# BMSMaster.net
KiCad netlist of a schematic drawn in EAGLE
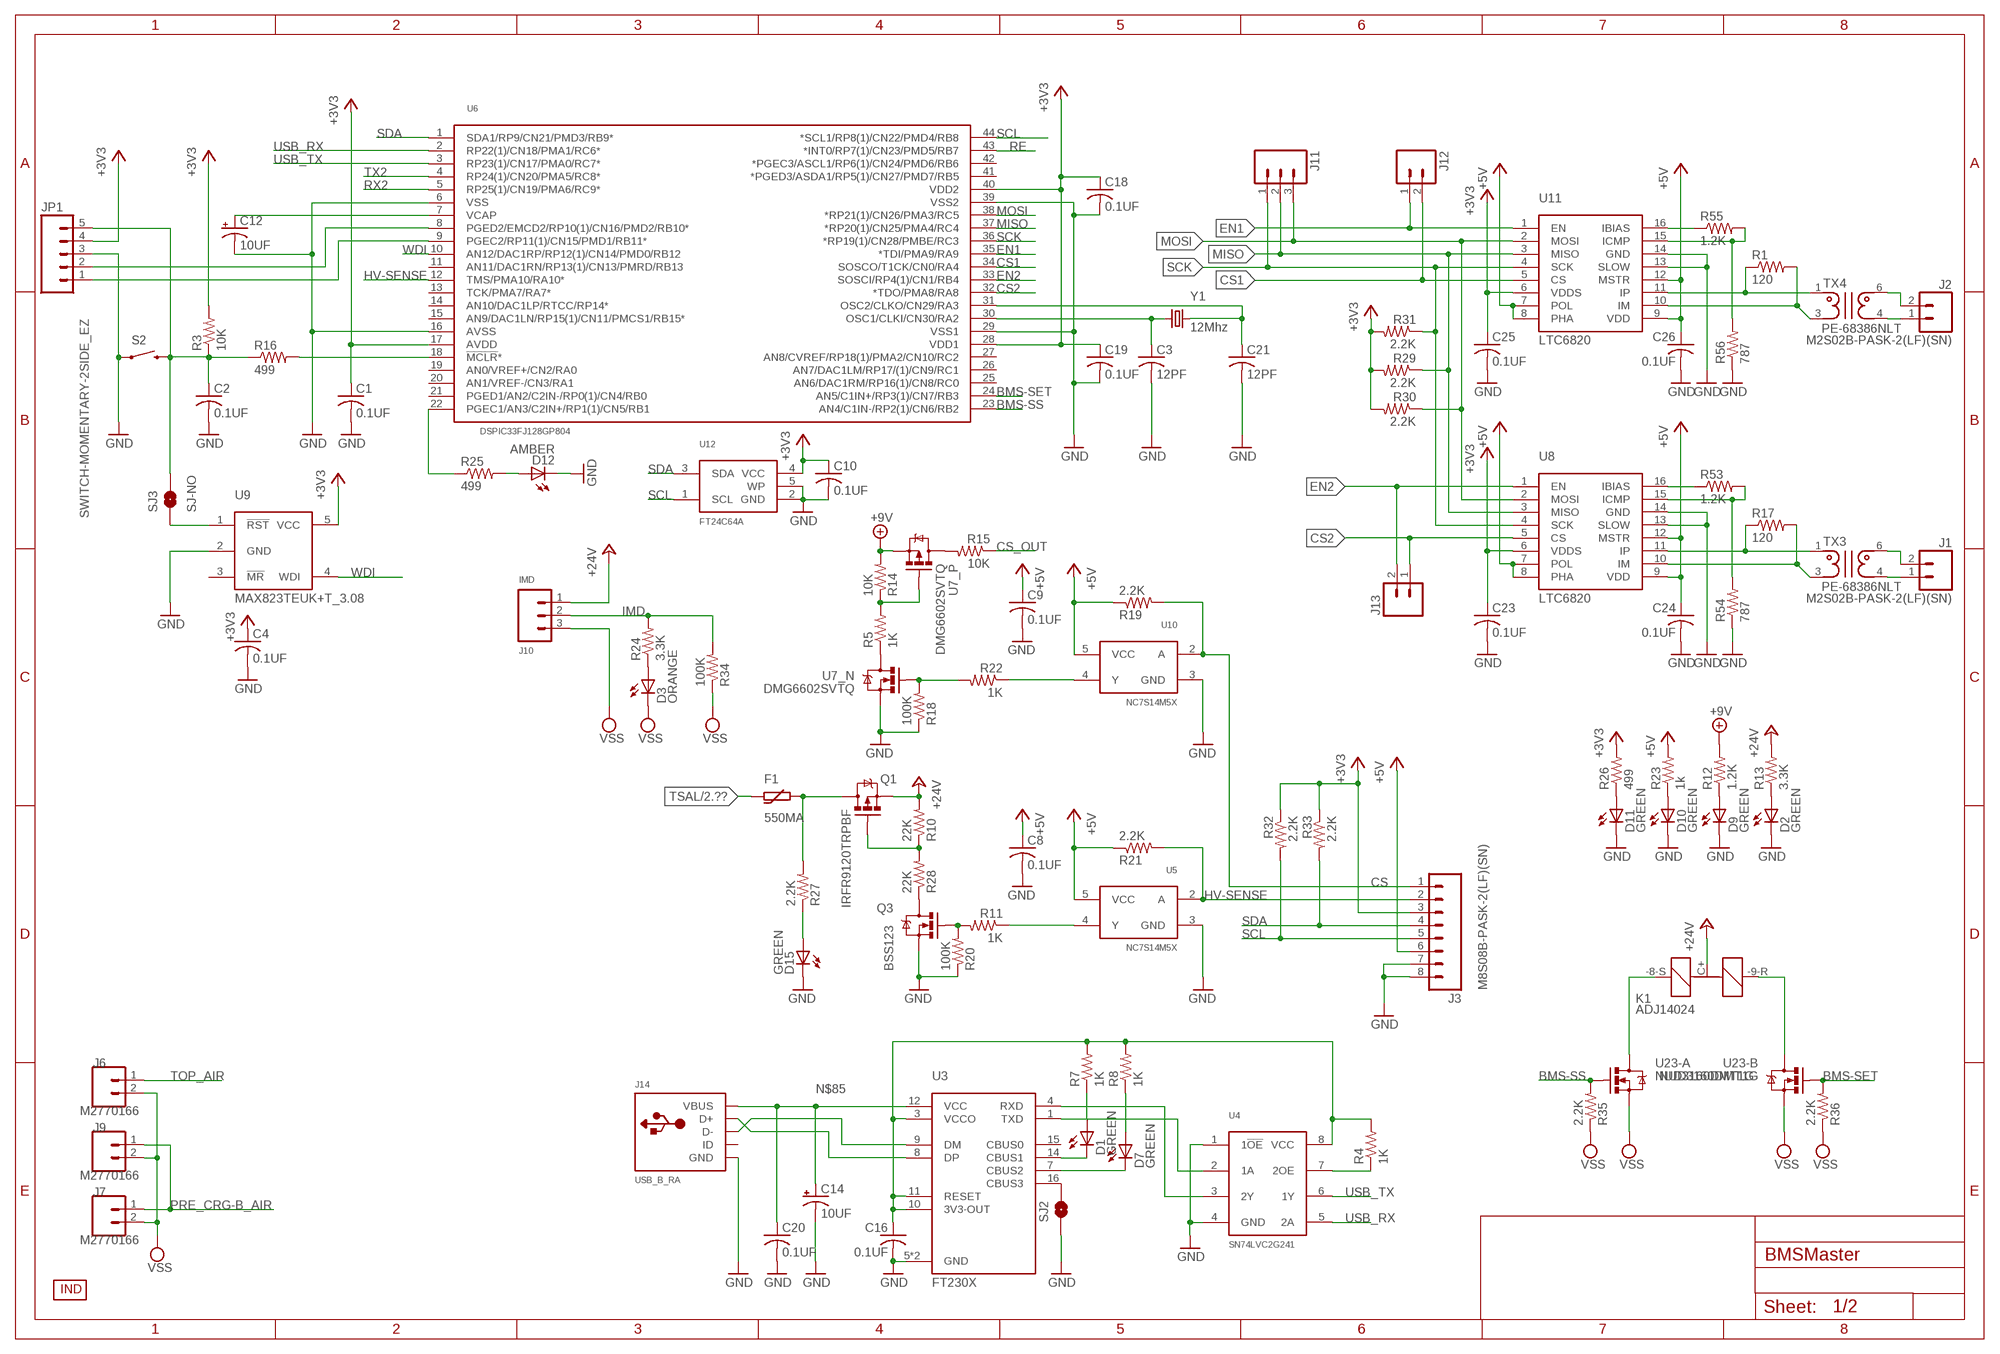
[diagram p0: schematic, sheet 1]
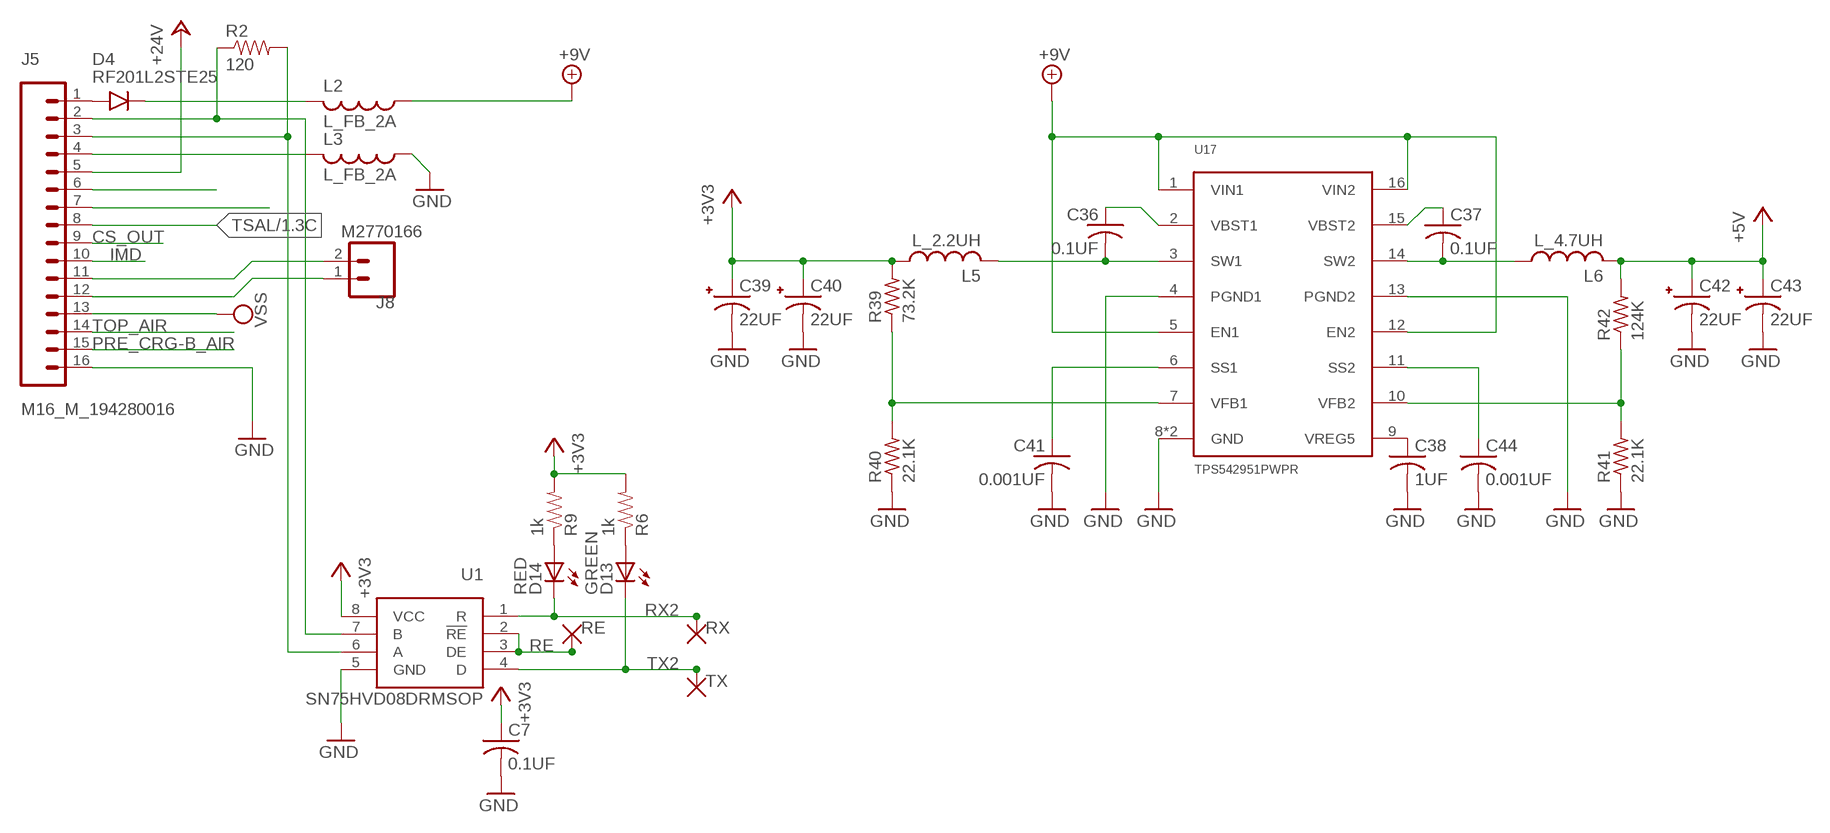
[diagram p1: schematic, sheet 2]

(export (version "E")
  (design (tool "Eeschema 10.0.6"))
  (components
    (comp (ref "C7")
      (value "0.1UF")
      (footprint "eagle-import:0805")
      (fields (field (name "PARTNO") "CC0805ZRY5V9BB104"))
      (libsource (lib "eagle-import") (part "CAP_0.1UF_50V_0805"))
    )
    (comp (ref "C36")
      (value "0.1UF")
      (footprint "eagle-import:R0603")
      (fields (field (name "PARTNO") "CC0603ZRY5V9BB104"))
      (libsource (lib "eagle-import") (part "C_0.1UF_50V"))
    )
    (comp (ref "C37")
      (value "0.1UF")
      (footprint "eagle-import:R0603")
      (fields (field (name "PARTNO") "CC0603ZRY5V9BB104"))
      (libsource (lib "eagle-import") (part "C_0.1UF_50V"))
    )
    (comp (ref "C38")
      (value "1UF")
      (footprint "eagle-import:R0603")
      (fields (field (name "PARTNO") "CL10B105MO8NNWC"))
      (libsource (lib "eagle-import") (part "C_1UF_16V"))
    )
    (comp (ref "C39")
      (value "22UF")
      (footprint "eagle-import:EIA7343")
      (fields (field (name "PARTNO") "T495D226K035ATE300"))
      (libsource (lib "eagle-import") (part "C-POL_22UF_35V"))
    )
    (comp (ref "C40")
      (value "22UF")
      (footprint "eagle-import:EIA7343")
      (fields (field (name "PARTNO") "T495D226K035ATE300"))
      (libsource (lib "eagle-import") (part "C-POL_22UF_35V"))
    )
    (comp (ref "C41")
      (value "0.001UF")
      (footprint "eagle-import:R0603")
      (fields (field (name "PARTNO") "GRM188R71H103KA01D"))
      (libsource (lib "eagle-import") (part "C_0.001UF_50V"))
    )
    (comp (ref "C42")
      (value "22UF")
      (footprint "eagle-import:EIA7343")
      (fields (field (name "PARTNO") "T495D226K035ATE300"))
      (libsource (lib "eagle-import") (part "C-POL_22UF_35V"))
    )
    (comp (ref "C43")
      (value "22UF")
      (footprint "eagle-import:EIA7343")
      (fields (field (name "PARTNO") "T495D226K035ATE300"))
      (libsource (lib "eagle-import") (part "C-POL_22UF_35V"))
    )
    (comp (ref "C44")
      (value "0.001UF")
      (footprint "eagle-import:R0603")
      (fields (field (name "PARTNO") "GRM188R71H103KA01D"))
      (libsource (lib "eagle-import") (part "C_0.001UF_50V"))
    )
    (comp (ref "D4")
      (value "RF201L2STE25")
      (footprint "eagle-import:SMA")
      (libsource (lib "eagle-import") (part "DIODE_RF201L2STE25"))
    )
    (comp (ref "D13")
      (value "GREEN")
      (footprint "eagle-import:CHIP_LED0805")
      (fields (field (name "PARTNO") "LTST-S220GKT"))
      (libsource (lib "eagle-import") (part "LED_GREEN"))
    )
    (comp (ref "D14")
      (value "RED")
      (footprint "eagle-import:CHIP_LED0805")
      (fields (field (name "PARTNO") "LH R974-LP-1"))
      (libsource (lib "eagle-import") (part "LED_RED"))
    )
    (comp (ref "J5")
      (value "M16_M_194280016")
      (footprint "eagle-import:19428-0016")
      (fields (field (name "PARTNO") "0194280016"))
      (libsource (lib "eagle-import") (part "M16_M_194280016"))
    )
    (comp (ref "J8")
      (value "M2770166")
      (footprint "eagle-import:1-770166-0")
      (fields (field (name "PARTNO") "1-770166-0"))
      (libsource (lib "eagle-import") (part "M2770166"))
    )
    (comp (ref "L2")
      (value "L_FB_2A")
      (footprint "eagle-import:0805")
      (fields (field (name "PARTNO") "FBMH2012HM121-T"))
      (libsource (lib "eagle-import") (part "L_FB_2A"))
    )
    (comp (ref "L3")
      (value "L_FB_2A")
      (footprint "eagle-import:0805")
      (fields (field (name "PARTNO") "FBMH2012HM121-T"))
      (libsource (lib "eagle-import") (part "L_FB_2A"))
    )
    (comp (ref "L5")
      (value "L_2.2UH")
      (footprint "eagle-import:LQH43")
      (fields (field (name "PARTNO") "LQH43PN2R2M26L"))
      (libsource (lib "eagle-import") (part "L_2.2UH"))
    )
    (comp (ref "L6")
      (value "L_4.7UH")
      (footprint "eagle-import:LQH43")
      (fields (field (name "PARTNO") " LQH43PN4R7M26L"))
      (libsource (lib "eagle-import") (part "L_4.7UH"))
    )
    (comp (ref "R2")
      (value "120")
      (footprint "eagle-import:0805")
      (fields (field (name "PARTNO") "RC0805FR-07120RL"))
      (libsource (lib "eagle-import") (part "RES_120_1%_0805"))
    )
    (comp (ref "R6")
      (value "1k")
      (footprint "eagle-import:0805")
      (fields (field (name "PARTNO") "RC0805FR-071KL"))
      (libsource (lib "eagle-import") (part "RES_1K_1%_0805"))
    )
    (comp (ref "R9")
      (value "1k")
      (footprint "eagle-import:0805")
      (fields (field (name "PARTNO") "RC0805FR-071KL"))
      (libsource (lib "eagle-import") (part "RES_1K_1%_0805"))
    )
    (comp (ref "R39")
      (value "73.2K")
      (footprint "eagle-import:R0805")
      (fields (field (name "PARTNO") " RC0805FR-0773K2L"))
      (libsource (lib "eagle-import") (part "R_73.2K_1%"))
    )
    (comp (ref "R40")
      (value "22.1K")
      (footprint "eagle-import:R0805")
      (fields (field (name "PARTNO") "RC0805FR-0722K1L"))
      (libsource (lib "eagle-import") (part "R_22.1K_1%"))
    )
    (comp (ref "R41")
      (value "22.1K")
      (footprint "eagle-import:R0805")
      (fields (field (name "PARTNO") "RC0805FR-0722K1L"))
      (libsource (lib "eagle-import") (part "R_22.1K_1%"))
    )
    (comp (ref "R42")
      (value "124K")
      (footprint "eagle-import:R0805")
      (fields (field (name "PARTNO") "RC0805FR-07124KL"))
      (libsource (lib "eagle-import") (part "R_124K_1%"))
    )
    (comp (ref "RE")
      (value "TP")
      (footprint "eagle-import:0603")
      (fields (field (name "PARTNO") "1625854-3"))
      (libsource (lib "eagle-import") (part "TP"))
    )
    (comp (ref "RX")
      (value "TP")
      (footprint "eagle-import:0603")
      (fields (field (name "PARTNO") "1625854-3"))
      (libsource (lib "eagle-import") (part "TP"))
    )
    (comp (ref "TX")
      (value "TP")
      (footprint "eagle-import:0603")
      (fields (field (name "PARTNO") "1625854-3"))
      (libsource (lib "eagle-import") (part "TP"))
    )
    (comp (ref "U1")
      (value "SN75HVD08DRMSOP")
      (footprint "eagle-import:MSOP-8")
      (fields (field (name "PARTNO") "ISL83072EIUZA-T"))
      (libsource (lib "eagle-import") (part "SN75HVD08DRMSOP"))
    )
    (comp (ref "U17")
      (value "TPS542951PWPR")
      (footprint "eagle-import:TSSOP-16")
      (libsource (lib "eagle-import") (part "TPS542951PWPR"))
    )
    (comp (ref "C1")
      (value "0.1UF")
      (footprint "eagle-import:0805")
      (fields (field (name "PARTNO") "CC0805ZRY5V9BB104"))
      (libsource (lib "eagle-import") (part "CAP_0.1UF_50V_0805"))
    )
    (comp (ref "C2")
      (value "0.1UF")
      (footprint "eagle-import:0805")
      (fields (field (name "PARTNO") "CC0805ZRY5V9BB104"))
      (libsource (lib "eagle-import") (part "CAP_0.1UF_50V_0805"))
    )
    (comp (ref "C3")
      (value "12PF")
      (footprint "eagle-import:0805")
      (fields (field (name "PARTNO") "CL21C120JBANNNC"))
      (libsource (lib "eagle-import") (part "CAP_12PF_50V_0805"))
    )
    (comp (ref "C4")
      (value "0.1UF")
      (footprint "eagle-import:0805")
      (fields (field (name "PARTNO") "CC0805ZRY5V9BB104"))
      (libsource (lib "eagle-import") (part "CAP_0.1UF_50V_0805"))
    )
    (comp (ref "C8")
      (value "0.1UF")
      (footprint "eagle-import:0805")
      (fields (field (name "PARTNO") "CC0805ZRY5V9BB104"))
      (libsource (lib "eagle-import") (part "CAP_0.1UF_50V_0805"))
    )
    (comp (ref "C9")
      (value "0.1UF")
      (footprint "eagle-import:0805")
      (fields (field (name "PARTNO") "CC0805ZRY5V9BB104"))
      (libsource (lib "eagle-import") (part "CAP_0.1UF_50V_0805"))
    )
    (comp (ref "C10")
      (value "0.1UF")
      (footprint "eagle-import:0805")
      (fields (field (name "PARTNO") "CC0805ZRY5V9BB104"))
      (libsource (lib "eagle-import") (part "CAP_0.1UF_50V_0805"))
    )
    (comp (ref "C12")
      (value "10UF")
      (footprint "eagle-import:EIA3216-16V")
      (fields (field (name "PARTNO") "T491A106M016AT"))
      (libsource (lib "eagle-import") (part "CAP-POL_10UF_16V"))
    )
    (comp (ref "C14")
      (value "10UF")
      (footprint "eagle-import:EIA3216-16V")
      (fields (field (name "PARTNO") "T491A106M016AT"))
      (libsource (lib "eagle-import") (part "CAP-POL_10UF_16V"))
    )
    (comp (ref "C16")
      (value "0.1UF")
      (footprint "eagle-import:0805")
      (fields (field (name "PARTNO") "CC0805ZRY5V9BB104"))
      (libsource (lib "eagle-import") (part "CAP_0.1UF_50V_0805"))
    )
    (comp (ref "C18")
      (value "0.1UF")
      (footprint "eagle-import:0805")
      (fields (field (name "PARTNO") "CC0805ZRY5V9BB104"))
      (libsource (lib "eagle-import") (part "CAP_0.1UF_50V_0805"))
    )
    (comp (ref "C19")
      (value "0.1UF")
      (footprint "eagle-import:0805")
      (fields (field (name "PARTNO") "CC0805ZRY5V9BB104"))
      (libsource (lib "eagle-import") (part "CAP_0.1UF_50V_0805"))
    )
    (comp (ref "C20")
      (value "0.1UF")
      (footprint "eagle-import:0805")
      (fields (field (name "PARTNO") "CC0805ZRY5V9BB104"))
      (libsource (lib "eagle-import") (part "CAP_0.1UF_50V_0805"))
    )
    (comp (ref "C21")
      (value "12PF")
      (footprint "eagle-import:0805")
      (fields (field (name "PARTNO") "CL21C120JBANNNC"))
      (libsource (lib "eagle-import") (part "CAP_12PF_50V_0805"))
    )
    (comp (ref "C23")
      (value "0.1UF")
      (footprint "eagle-import:0805")
      (fields (field (name "PARTNO") "CC0805ZRY5V9BB104"))
      (libsource (lib "eagle-import") (part "CAP_0.1UF_50V_0805"))
    )
    (comp (ref "C24")
      (value "0.1UF")
      (footprint "eagle-import:0805")
      (fields (field (name "PARTNO") "CC0805ZRY5V9BB104"))
      (libsource (lib "eagle-import") (part "CAP_0.1UF_50V_0805"))
    )
    (comp (ref "C25")
      (value "0.1UF")
      (footprint "eagle-import:0805")
      (fields (field (name "PARTNO") "CC0805ZRY5V9BB104"))
      (libsource (lib "eagle-import") (part "CAP_0.1UF_50V_0805"))
    )
    (comp (ref "C26")
      (value "0.1UF")
      (footprint "eagle-import:0805")
      (fields (field (name "PARTNO") "CC0805ZRY5V9BB104"))
      (libsource (lib "eagle-import") (part "CAP_0.1UF_50V_0805"))
    )
    (comp (ref "D1")
      (value "GREEN")
      (footprint "eagle-import:CHIP_LED0805")
      (fields (field (name "PARTNO") "LTST-S220GKT"))
      (libsource (lib "eagle-import") (part "LED_GREEN"))
    )
    (comp (ref "D2")
      (value "GREEN")
      (footprint "eagle-import:CHIP_LED0805")
      (fields (field (name "PARTNO") "LTST-S220GKT"))
      (libsource (lib "eagle-import") (part "LED_GREEN"))
    )
    (comp (ref "D3")
      (value "ORANGE")
      (footprint "eagle-import:CHIP_LED0805")
      (fields (field (name "PARTNO") "LTST-C170KFKT"))
      (libsource (lib "eagle-import") (part "LED_ORANGE"))
    )
    (comp (ref "D7")
      (value "GREEN")
      (footprint "eagle-import:CHIP_LED0805")
      (fields (field (name "PARTNO") "LTST-S220GKT"))
      (libsource (lib "eagle-import") (part "LED_GREEN"))
    )
    (comp (ref "D9")
      (value "GREEN")
      (footprint "eagle-import:CHIP_LED0805")
      (fields (field (name "PARTNO") "LTST-S220GKT"))
      (libsource (lib "eagle-import") (part "LED_GREEN"))
    )
    (comp (ref "D10")
      (value "GREEN")
      (footprint "eagle-import:CHIP_LED0805")
      (fields (field (name "PARTNO") "LTST-S220GKT"))
      (libsource (lib "eagle-import") (part "LED_GREEN"))
    )
    (comp (ref "D11")
      (value "GREEN")
      (footprint "eagle-import:CHIP_LED0805")
      (fields (field (name "PARTNO") "LTST-S220GKT"))
      (libsource (lib "eagle-import") (part "LED_GREEN"))
    )
    (comp (ref "D12")
      (value "AMBER")
      (footprint "eagle-import:CHIP_LED0805")
      (fields (field (name "PARTNO") "HSMA-C170"))
      (libsource (lib "eagle-import") (part "LED_AMBER"))
    )
    (comp (ref "D15")
      (value "GREEN")
      (footprint "eagle-import:CHIP_LED0805")
      (fields (field (name "PARTNO") "LTST-S220GKT"))
      (libsource (lib "eagle-import") (part "LED_GREEN"))
    )
    (comp (ref "F1")
      (value "550MA")
      (footprint "eagle-import:2018")
      (fields (field (name "PARTNO") "MF-SMDF050-2"))
      (libsource (lib "eagle-import") (part "PTC_550MA_60V"))
    )
    (comp (ref "J1")
      (value "M2S02B-PASK-2(LF)(SN)")
      (footprint "eagle-import:S02B-PASK-2(LF)(SN)")
      (fields (field (name "PARTNO") "S02B-PASK-2(LF)(SN)"))
      (libsource (lib "eagle-import") (part "M2S02B-PASK-2(LF)(SN)"))
    )
    (comp (ref "J2")
      (value "M2S02B-PASK-2(LF)(SN)")
      (footprint "eagle-import:S02B-PASK-2(LF)(SN)")
      (fields (field (name "PARTNO") "S02B-PASK-2(LF)(SN)"))
      (libsource (lib "eagle-import") (part "M2S02B-PASK-2(LF)(SN)"))
    )
    (comp (ref "J3")
      (value "M8S08B-PASK-2(LF)(SN)")
      (footprint "eagle-import:S08B-PASK-2(LF)(SN)")
      (fields (field (name "PARTNO") "S08B-PASK-2(LF)(SN)"))
      (libsource (lib "eagle-import") (part "M8S08B-PASK-2(LF)(SN)"))
    )
    (comp (ref "J6")
      (value "M2770166")
      (footprint "eagle-import:1-770166-0")
      (fields (field (name "PARTNO") "1-770166-0"))
      (libsource (lib "eagle-import") (part "M2770166"))
    )
    (comp (ref "J7")
      (value "M2770166")
      (footprint "eagle-import:1-770166-0")
      (fields (field (name "PARTNO") "1-770166-0"))
      (libsource (lib "eagle-import") (part "M2770166"))
    )
    (comp (ref "J9")
      (value "M2770166")
      (footprint "eagle-import:1-770166-0")
      (fields (field (name "PARTNO") "1-770166-0"))
      (libsource (lib "eagle-import") (part "M2770166"))
    )
    (comp (ref "J10")
      (value "IMD")
      (footprint "eagle-import:MOLEX-1X3")
      (fields (field (name "PARTNO") "0022232031"))
      (libsource (lib "eagle-import") (part "M3M1X3"))
    )
    (comp (ref "J11")
      (value "M03LOCK_LONGPADS")
      (footprint "eagle-import:1X03_LOCK_LONGPADS")
      (libsource (lib "eagle-import") (part "M03LOCK_LONGPADS"))
    )
    (comp (ref "J12")
      (value "M02LOCK_LONGPADS")
      (footprint "eagle-import:1X02_LOCK_LONGPADS")
      (libsource (lib "eagle-import") (part "M02LOCK_LONGPADS"))
    )
    (comp (ref "J13")
      (value "M02LOCK_LONGPADS")
      (footprint "eagle-import:1X02_LOCK_LONGPADS")
      (libsource (lib "eagle-import") (part "M02LOCK_LONGPADS"))
    )
    (comp (ref "J14")
      (value "USB_B_RA")
      (footprint "eagle-import:USB-B1HSW6")
      (fields (field (name "PARTNO") "USB-B1HSW6"))
      (libsource (lib "eagle-import") (part "USB_B_RA"))
    )
    (comp (ref "JP1")
      (value "M05LOCK_LONGPADS")
      (footprint "eagle-import:1X05_LOCK_LONGPADS")
      (libsource (lib "eagle-import") (part "M05LOCK_LONGPADS"))
    )
    (comp (ref "K1")
      (value "ADJ14024")
      (footprint "eagle-import:ADJ14024")
      (libsource (lib "eagle-import") (part "ADJ14024"))
    )
    (comp (ref "Q1")
      (value "IRFR9120TRPBF")
      (footprint "eagle-import:DPAK")
      (libsource (lib "eagle-import") (part "MOS-P_IRFR9120TRPBF"))
    )
    (comp (ref "Q3")
      (value "BSS123")
      (footprint "eagle-import:SOT23")
      (fields (field (name "PARTNO") "BSS123,215"))
      (libsource (lib "eagle-import") (part "MOS-N_BSS123"))
    )
    (comp (ref "R1")
      (value "120")
      (footprint "eagle-import:0805")
      (fields (field (name "PARTNO") "RC0805FR-07120RL"))
      (libsource (lib "eagle-import") (part "RES_120_1%_0805"))
    )
    (comp (ref "R3")
      (value "10K")
      (footprint "eagle-import:0805")
      (fields (field (name "PARTNO") "RC0805FR-0710KL"))
      (libsource (lib "eagle-import") (part "RES_10K_1%_0805"))
    )
    (comp (ref "R4")
      (value "1K")
      (footprint "eagle-import:0805")
      (fields (field (name "PARTNO") "RC0805FR-071KL"))
      (libsource (lib "eagle-import") (part "RES_1K_1%_0805"))
    )
    (comp (ref "R5")
      (value "1K")
      (footprint "eagle-import:0805")
      (fields (field (name "PARTNO") "RC0805FR-071KL"))
      (libsource (lib "eagle-import") (part "RES_1K_1%_0805"))
    )
    (comp (ref "R7")
      (value "1K")
      (footprint "eagle-import:0805")
      (fields (field (name "PARTNO") "RC0805FR-071KL"))
      (libsource (lib "eagle-import") (part "RES_1K_1%_0805"))
    )
    (comp (ref "R8")
      (value "1K")
      (footprint "eagle-import:0805")
      (fields (field (name "PARTNO") "RC0805FR-071KL"))
      (libsource (lib "eagle-import") (part "RES_1K_1%_0805"))
    )
    (comp (ref "R10")
      (value "22K")
      (footprint "eagle-import:0805")
      (fields (field (name "PARTNO") "RC0805FR-0722KL"))
      (libsource (lib "eagle-import") (part "RES_22K_1%_0805"))
    )
    (comp (ref "R11")
      (value "1K")
      (footprint "eagle-import:0805")
      (fields (field (name "PARTNO") "RC0805FR-071KL"))
      (libsource (lib "eagle-import") (part "RES_1K_1%_0805"))
    )
    (comp (ref "R12")
      (value "1.2K")
      (footprint "eagle-import:0805")
      (fields (field (name "PARTNO") "RC0805FR-071K2L"))
      (libsource (lib "eagle-import") (part "RES_1.2K_1%_0805"))
    )
    (comp (ref "R13")
      (value "3.3K")
      (footprint "eagle-import:0805")
      (fields (field (name "PARTNO") "RC0805FR-073K3L"))
      (libsource (lib "eagle-import") (part "RES_3.3K_1%_0805"))
    )
    (comp (ref "R14")
      (value "10K")
      (footprint "eagle-import:0805")
      (fields (field (name "PARTNO") "RC0805FR-0710KL"))
      (libsource (lib "eagle-import") (part "RES_10K_1%_0805"))
    )
    (comp (ref "R15")
      (value "10K")
      (footprint "eagle-import:0805")
      (fields (field (name "PARTNO") "RC0805FR-0710KL"))
      (libsource (lib "eagle-import") (part "RES_10K_1%_0805"))
    )
    (comp (ref "R16")
      (value "499")
      (footprint "eagle-import:0805")
      (fields (field (name "PARTNO") "RC0805FR-07499RL"))
      (libsource (lib "eagle-import") (part "RES_499_1%_0805"))
    )
    (comp (ref "R17")
      (value "120")
      (footprint "eagle-import:0805")
      (fields (field (name "PARTNO") "RC0805FR-07120RL"))
      (libsource (lib "eagle-import") (part "RES_120_1%_0805"))
    )
    (comp (ref "R18")
      (value "100K")
      (footprint "eagle-import:0805")
      (fields (field (name "PARTNO") "RC0805FR-07100KL"))
      (libsource (lib "eagle-import") (part "RES_100K_1%_0805"))
    )
    (comp (ref "R19")
      (value "2.2K")
      (footprint "eagle-import:0805")
      (fields (field (name "PARTNO") "RC0805FR-072K2L"))
      (libsource (lib "eagle-import") (part "RES_2.2K_1%_0805"))
    )
    (comp (ref "R20")
      (value "100K")
      (footprint "eagle-import:0805")
      (fields (field (name "PARTNO") "RC0805FR-07100KL"))
      (libsource (lib "eagle-import") (part "RES_100K_1%_0805"))
    )
    (comp (ref "R21")
      (value "2.2K")
      (footprint "eagle-import:0805")
      (fields (field (name "PARTNO") "RC0805FR-072K2L"))
      (libsource (lib "eagle-import") (part "RES_2.2K_1%_0805"))
    )
    (comp (ref "R22")
      (value "1K")
      (footprint "eagle-import:0805")
      (fields (field (name "PARTNO") "RC0805FR-071KL"))
      (libsource (lib "eagle-import") (part "RES_1K_1%_0805"))
    )
    (comp (ref "R23")
      (value "1k")
      (footprint "eagle-import:0805")
      (fields (field (name "PARTNO") "RC0805FR-071KL"))
      (libsource (lib "eagle-import") (part "RES_1K_1%_0805"))
    )
    (comp (ref "R24")
      (value "3.3K")
      (footprint "eagle-import:0805")
      (fields (field (name "PARTNO") "RC0805FR-073K3L"))
      (libsource (lib "eagle-import") (part "RES_3.3K_1%_0805"))
    )
    (comp (ref "R25")
      (value "499")
      (footprint "eagle-import:0805")
      (fields (field (name "PARTNO") "RC0805FR-07499RL"))
      (libsource (lib "eagle-import") (part "RES_499_1%_0805"))
    )
    (comp (ref "R26")
      (value "499")
      (footprint "eagle-import:0805")
      (fields (field (name "PARTNO") "RC0805FR-07499RL"))
      (libsource (lib "eagle-import") (part "RES_499_1%_0805"))
    )
    (comp (ref "R27")
      (value "2.2K")
      (footprint "eagle-import:0805")
      (fields (field (name "PARTNO") "RC0805FR-072K2L"))
      (libsource (lib "eagle-import") (part "RES_2.2K_1%_0805"))
    )
    (comp (ref "R28")
      (value "22K")
      (footprint "eagle-import:0805")
      (fields (field (name "PARTNO") "RC0805FR-0722KL"))
      (libsource (lib "eagle-import") (part "RES_22K_1%_0805"))
    )
    (comp (ref "R29")
      (value "2.2K")
      (footprint "eagle-import:0805")
      (fields (field (name "PARTNO") "RC0805FR-072K2L"))
      (libsource (lib "eagle-import") (part "RES_2.2K_1%_0805"))
    )
    (comp (ref "R30")
      (value "2.2K")
      (footprint "eagle-import:0805")
      (fields (field (name "PARTNO") "RC0805FR-072K2L"))
      (libsource (lib "eagle-import") (part "RES_2.2K_1%_0805"))
    )
    (comp (ref "R31")
      (value "2.2K")
      (footprint "eagle-import:0805")
      (fields (field (name "PARTNO") "RC0805FR-072K2L"))
      (libsource (lib "eagle-import") (part "RES_2.2K_1%_0805"))
    )
    (comp (ref "R32")
      (value "2.2K")
      (footprint "eagle-import:0805")
      (fields (field (name "PARTNO") "RC0805FR-072K2L"))
      (libsource (lib "eagle-import") (part "RES_2.2K_1%_0805"))
    )
    (comp (ref "R33")
      (value "2.2K")
      (footprint "eagle-import:0805")
      (fields (field (name "PARTNO") "RC0805FR-072K2L"))
      (libsource (lib "eagle-import") (part "RES_2.2K_1%_0805"))
    )
    (comp (ref "R34")
      (value "100K")
      (footprint "eagle-import:0805")
      (fields (field (name "PARTNO") "RC0805FR-07100KL"))
      (libsource (lib "eagle-import") (part "RES_100K_1%_0805"))
    )
    (comp (ref "R35")
      (value "2.2K")
      (footprint "eagle-import:0805")
      (fields (field (name "PARTNO") "RC0805FR-072K2L"))
      (libsource (lib "eagle-import") (part "RES_2.2K_1%_0805"))
    )
    (comp (ref "R36")
      (value "2.2K")
      (footprint "eagle-import:0805")
      (fields (field (name "PARTNO") "RC0805FR-072K2L"))
      (libsource (lib "eagle-import") (part "RES_2.2K_1%_0805"))
    )
    (comp (ref "R53")
      (value "1.2K")
      (footprint "eagle-import:0805")
      (fields (field (name "PARTNO") "RC0805FR-071K2L"))
      (libsource (lib "eagle-import") (part "RES_1.2K_1%_0805"))
    )
    (comp (ref "R54")
      (value "787")
      (footprint "eagle-import:0805")
      (fields (field (name "PARTNO") "RC0805FR-07787RL"))
      (libsource (lib "eagle-import") (part "RES_787_1%"))
    )
    (comp (ref "R55")
      (value "1.2K")
      (footprint "eagle-import:0805")
      (fields (field (name "PARTNO") "RC0805FR-071K2L"))
      (libsource (lib "eagle-import") (part "RES_1.2K_1%_0805"))
    )
    (comp (ref "R56")
      (value "787")
      (footprint "eagle-import:0805")
      (fields (field (name "PARTNO") "RC0805FR-07787RL"))
      (libsource (lib "eagle-import") (part "RES_787_1%"))
    )
    (comp (ref "S2")
      (value "SWITCH-MOMENTARY-2SIDE_EZ")
      (footprint "eagle-import:TACTILE-PTH-SIDEEZ")
      (fields (field (name "PARTNO") "3-1825910-5"))
      (libsource (lib "eagle-import") (part "SWITCH-MOMENTARY-2SIDE_EZ"))
    )
    (comp (ref "SJ2")
      (value "JUMPER-PAD-2-NOYES_SILK")
      (footprint "eagle-import:PAD-JUMPER-2-NO_YES_SILK")
      (libsource (lib "eagle-import") (part "JUMPER-PAD-2-NOYES_SILK"))
    )
    (comp (ref "SJ3")
      (value "SJ-NO")
      (footprint "eagle-import:SJ_2S-NO")
      (libsource (lib "eagle-import") (part "SOLDERJUMPERNO"))
    )
    (comp (ref "TX3")
      (value "PE-68386NLT")
      (footprint "eagle-import:PE-68386NLT")
      (libsource (lib "eagle-import") (part "PE-68386NLT"))
    )
    (comp (ref "TX4")
      (value "PE-68386NLT")
      (footprint "eagle-import:PE-68386NLT")
      (libsource (lib "eagle-import") (part "PE-68386NLT"))
    )
    (comp (ref "U$1")
      (value "INDPK1")
      (footprint "eagle-import:PICKIT-PIN-1")
      (libsource (lib "eagle-import") (part "INDPK1"))
    )
    (comp (ref "U3")
      (value "FT230X")
      (footprint "eagle-import:SSOP-16")
      (fields (field (name "PARTNO") "FT230XS-R"))
      (libsource (lib "eagle-import") (part "FT230X"))
    )
    (comp (ref "U4")
      (value "SN74LVC2G241")
      (footprint "eagle-import:VFSOP-8")
      (fields (field (name "PARTNO") "SN74LVC2G241DCUR"))
      (libsource (lib "eagle-import") (part "SN74LVC2G241"))
    )
    (comp (ref "U5")
      (value "NC7S14M5X")
      (footprint "eagle-import:SOT23-5")
      (libsource (lib "eagle-import") (part "NC7S14M5X"))
    )
    (comp (ref "U6")
      (value "DSPIC33FJ128GP804")
      (footprint "eagle-import:TQFP-44")
      (fields (field (name "PARTNO") "DSPIC33FJ128GP804-I/PT"))
      (libsource (lib "eagle-import") (part "DSPIC33FJ128GP804"))
    )
    (comp (ref "U7")
      (value "DMG6602SVTQ")
      (footprint "eagle-import:SOT23-6")
      (fields (field (name "PARTNO") "DMG6602SVTQ-7"))
      (libsource (lib "eagle-import") (part "DMG6602SVTQ"))
    )
    (comp (ref "U8")
      (value "LTC6820")
      (footprint "eagle-import:MSOP-16")
      (fields (field (name "PARTNO") "LTC6820IMS#PBF"))
      (libsource (lib "eagle-import") (part "LTC6820"))
    )
    (comp (ref "U9")
      (value "MAX823TEUK+T_3.08")
      (footprint "eagle-import:SOT23-5")
      (fields (field (name "PARTNO") "MAX823TEUK+T"))
      (libsource (lib "eagle-import") (part "MAX823TEUK+T_3.08"))
    )
    (comp (ref "U10")
      (value "NC7S14M5X")
      (footprint "eagle-import:SOT23-5")
      (libsource (lib "eagle-import") (part "NC7S14M5X"))
    )
    (comp (ref "U11")
      (value "LTC6820")
      (footprint "eagle-import:MSOP-16")
      (fields (field (name "PARTNO") "LTC6820IMS#PBF"))
      (libsource (lib "eagle-import") (part "LTC6820"))
    )
    (comp (ref "U12")
      (value "FT24C64A")
      (footprint "eagle-import:SOT23-5")
      (fields (field (name "PARTNO") "FT24C64A-ULR-T"))
      (libsource (lib "eagle-import") (part "FT24C64A"))
    )
    (comp (ref "U23")
      (value "NUD3160DMT1G")
      (footprint "eagle-import:SC74-6")
      (libsource (lib "eagle-import") (part "NUD3160DMT1G"))
    )
    (comp (ref "Y1")
      (value "12Mhz")
      (footprint "eagle-import:CRYSTAL-SMD-5X3")
      (libsource (lib "eagle-import") (part "CRYSTAL5X3"))
    )
  )
  (nets
    (net (code "1") (name "+3V3") (class "Default")
      (node (ref "C1") (pin "1") (pinfunction "+_1") (pintype "passive"))
      (node (ref "C10") (pin "1") (pinfunction "+_1") (pintype "passive"))
      (node (ref "C18") (pin "1") (pinfunction "+_1") (pintype "passive"))
      (node (ref "C19") (pin "1") (pinfunction "+_1") (pintype "passive"))
      (node (ref "C23") (pin "1") (pinfunction "+_1") (pintype "passive"))
      (node (ref "C25") (pin "1") (pinfunction "+_1") (pintype "passive"))
      (node (ref "C39") (pin "+") (pinfunction "+_+") (pintype "passive"))
      (node (ref "C4") (pin "1") (pinfunction "+_1") (pintype "passive"))
      (node (ref "C40") (pin "+") (pinfunction "+_+") (pintype "passive"))
      (node (ref "C7") (pin "1") (pinfunction "+_1") (pintype "passive"))
      (node (ref "J3") (pin "3") (pinfunction "3_3") (pintype "passive"))
      (node (ref "JP1") (pin "4") (pinfunction "4_4") (pintype "passive"))
      (node (ref "L5") (pin "1") (pinfunction "1_1") (pintype "passive"))
      (node (ref "R26") (pin "2") (pinfunction "2_2") (pintype "passive"))
      (node (ref "R29") (pin "2") (pinfunction "2_2") (pintype "passive"))
      (node (ref "R3") (pin "2") (pinfunction "2_2") (pintype "passive"))
      (node (ref "R30") (pin "2") (pinfunction "2_2") (pintype "passive"))
      (node (ref "R31") (pin "2") (pinfunction "2_2") (pintype "passive"))
      (node (ref "R32") (pin "1") (pinfunction "1_1") (pintype "passive"))
      (node (ref "R33") (pin "1") (pinfunction "1_1") (pintype "passive"))
      (node (ref "R39") (pin "2") (pinfunction "2_2") (pintype "passive"))
      (node (ref "R6") (pin "2") (pinfunction "2_2") (pintype "passive"))
      (node (ref "R9") (pin "2") (pinfunction "2_2") (pintype "passive"))
      (node (ref "U1") (pin "8") (pinfunction "VCC_8") (pintype "bidirectional"))
      (node (ref "U11") (pin "6") (pinfunction "VDDS_6") (pintype "bidirectional"))
      (node (ref "U12") (pin "4") (pinfunction "VCC_4") (pintype "bidirectional"))
      (node (ref "U6") (pin "17") (pinfunction "AVDD_17") (pintype "bidirectional"))
      (node (ref "U6") (pin "28") (pinfunction "VDD1_28") (pintype "bidirectional"))
      (node (ref "U6") (pin "40") (pinfunction "VDD2_40") (pintype "bidirectional"))
      (node (ref "U8") (pin "6") (pinfunction "VDDS_6") (pintype "bidirectional"))
      (node (ref "U9") (pin "5") (pinfunction "VCC_5") (pintype "bidirectional"))
    )
    (net (code "2") (name "+5V") (class "Default")
      (node (ref "C24") (pin "1") (pinfunction "+_1") (pintype "passive"))
      (node (ref "C26") (pin "1") (pinfunction "+_1") (pintype "passive"))
      (node (ref "C42") (pin "+") (pinfunction "+_+") (pintype "passive"))
      (node (ref "C43") (pin "+") (pinfunction "+_+") (pintype "passive"))
      (node (ref "C8") (pin "1") (pinfunction "+_1") (pintype "passive"))
      (node (ref "C9") (pin "1") (pinfunction "+_1") (pintype "passive"))
      (node (ref "J3") (pin "6") (pinfunction "6_6") (pintype "passive"))
      (node (ref "L6") (pin "2") (pinfunction "2_2") (pintype "passive"))
      (node (ref "R19") (pin "1") (pinfunction "1_1") (pintype "passive"))
      (node (ref "R21") (pin "1") (pinfunction "1_1") (pintype "passive"))
      (node (ref "R23") (pin "2") (pinfunction "2_2") (pintype "passive"))
      (node (ref "R42") (pin "2") (pinfunction "2_2") (pintype "passive"))
      (node (ref "U10") (pin "5") (pinfunction "VCC_5") (pintype "bidirectional"))
      (node (ref "U11") (pin "12") (pinfunction "MSTR_12") (pintype "bidirectional"))
      (node (ref "U11") (pin "7") (pinfunction "POL_7") (pintype "bidirectional"))
      (node (ref "U11") (pin "8") (pinfunction "PHA_8") (pintype "bidirectional"))
      (node (ref "U11") (pin "9") (pinfunction "VDD_9") (pintype "bidirectional"))
      (node (ref "U5") (pin "5") (pinfunction "VCC_5") (pintype "bidirectional"))
      (node (ref "U8") (pin "12") (pinfunction "MSTR_12") (pintype "bidirectional"))
      (node (ref "U8") (pin "7") (pinfunction "POL_7") (pintype "bidirectional"))
      (node (ref "U8") (pin "8") (pinfunction "PHA_8") (pintype "bidirectional"))
      (node (ref "U8") (pin "9") (pinfunction "VDD_9") (pintype "bidirectional"))
    )
    (net (code "3") (name "+9V") (class "Default")
      (node (ref "L2") (pin "1") (pinfunction "1_1") (pintype "passive"))
      (node (ref "R12") (pin "2") (pinfunction "2_2") (pintype "passive"))
      (node (ref "R14") (pin "2") (pinfunction "2_2") (pintype "passive"))
      (node (ref "U17") (pin "1") (pinfunction "VIN1_1") (pintype "bidirectional"))
      (node (ref "U17") (pin "12") (pinfunction "EN2_12") (pintype "bidirectional"))
      (node (ref "U17") (pin "16") (pinfunction "VIN2_16") (pintype "bidirectional"))
      (node (ref "U17") (pin "5") (pinfunction "EN1_5") (pintype "bidirectional"))
      (node (ref "U7") (pin "2") (pinfunction "S_2") (pintype "passive"))
    )
    (net (code "4") (name "+24V") (class "Default")
      (node (ref "J10") (pin "1") (pinfunction "P$1_1") (pintype "bidirectional"))
      (node (ref "J5") (pin "5") (pinfunction "5_5") (pintype "passive"))
      (node (ref "K1") (pin "C+") (pinfunction "-_C+") (pintype "passive"))
      (node (ref "Q1") (pin "3") (pinfunction "S_3") (pintype "passive"))
      (node (ref "R10") (pin "2") (pinfunction "2_2") (pintype "passive"))
      (node (ref "R13") (pin "2") (pinfunction "2_2") (pintype "passive"))
    )
    (net (code "5") (name "BMS-SET") (class "Default")
      (node (ref "R36") (pin "2") (pinfunction "2_2") (pintype "passive"))
      (node (ref "U23") (pin "5") (pinfunction "G_5") (pintype "passive"))
      (node (ref "U6") (pin "24") (pinfunction "AN5/C1IN+/RP3(1)/CN7/RB3_24") (pintype "bidirectional"))
    )
    (net (code "6") (name "BMS-SS") (class "Default")
      (node (ref "R35") (pin "2") (pinfunction "2_2") (pintype "passive"))
      (node (ref "U23") (pin "2") (pinfunction "G_2") (pintype "passive"))
      (node (ref "U6") (pin "23") (pinfunction "AN4/C1IN-/RP2(1)/CN6/RB2_23") (pintype "bidirectional"))
    )
    (net (code "7") (name "CS") (class "Default")
      (node (ref "J3") (pin "1") (pinfunction "1_1") (pintype "passive"))
      (node (ref "R19") (pin "2") (pinfunction "2_2") (pintype "passive"))
      (node (ref "U10") (pin "2") (pinfunction "A_2") (pintype "bidirectional"))
    )
    (net (code "8") (name "CS1") (class "Default")
      (node (ref "J12") (pin "2") (pinfunction "2_2") (pintype "passive"))
      (node (ref "U11") (pin "5") (pinfunction "CS_5") (pintype "bidirectional"))
      (node (ref "U6") (pin "34") (pinfunction "SOSCO/T1CK/CN0/RA4_34") (pintype "bidirectional"))
    )
    (net (code "9") (name "CS2") (class "Default")
      (node (ref "J13") (pin "1") (pinfunction "1_1") (pintype "passive"))
      (node (ref "U6") (pin "32") (pinfunction "*TDO/PMA8/RA8_32") (pintype "bidirectional"))
      (node (ref "U8") (pin "5") (pinfunction "CS_5") (pintype "bidirectional"))
    )
    (net (code "10") (name "CS_OUT") (class "Default")
      (node (ref "J5") (pin "9") (pinfunction "9_9") (pintype "passive"))
      (node (ref "R15") (pin "1") (pinfunction "1_1") (pintype "passive"))
    )
    (net (code "11") (name "EN1") (class "Default")
      (node (ref "J12") (pin "1") (pinfunction "1_1") (pintype "passive"))
      (node (ref "U11") (pin "1") (pinfunction "EN_1") (pintype "bidirectional"))
      (node (ref "U6") (pin "35") (pinfunction "*TDI/PMA9/RA9_35") (pintype "bidirectional"))
    )
    (net (code "12") (name "EN2") (class "Default")
      (node (ref "J13") (pin "2") (pinfunction "2_2") (pintype "passive"))
      (node (ref "U6") (pin "33") (pinfunction "SOSCI/RP4(1)/CN1/RB4_33") (pintype "bidirectional"))
      (node (ref "U8") (pin "1") (pinfunction "EN_1") (pintype "bidirectional"))
    )
    (net (code "13") (name "GND") (class "Default")
      (node (ref "C1") (pin "2") (pinfunction "-_2") (pintype "passive"))
      (node (ref "C10") (pin "2") (pinfunction "-_2") (pintype "passive"))
      (node (ref "C12") (pin "C") (pinfunction "-_C") (pintype "passive"))
      (node (ref "C14") (pin "C") (pinfunction "-_C") (pintype "passive"))
      (node (ref "C16") (pin "2") (pinfunction "-_2") (pintype "passive"))
      (node (ref "C18") (pin "2") (pinfunction "-_2") (pintype "passive"))
      (node (ref "C19") (pin "2") (pinfunction "-_2") (pintype "passive"))
      (node (ref "C2") (pin "2") (pinfunction "-_2") (pintype "passive"))
      (node (ref "C20") (pin "2") (pinfunction "-_2") (pintype "passive"))
      (node (ref "C21") (pin "2") (pinfunction "-_2") (pintype "passive"))
      (node (ref "C23") (pin "2") (pinfunction "-_2") (pintype "passive"))
      (node (ref "C24") (pin "2") (pinfunction "-_2") (pintype "passive"))
      (node (ref "C25") (pin "2") (pinfunction "-_2") (pintype "passive"))
      (node (ref "C26") (pin "2") (pinfunction "-_2") (pintype "passive"))
      (node (ref "C3") (pin "2") (pinfunction "-_2") (pintype "passive"))
      (node (ref "C38") (pin "2") (pinfunction "2_2") (pintype "passive"))
      (node (ref "C39") (pin "-") (pinfunction "-_-") (pintype "passive"))
      (node (ref "C4") (pin "2") (pinfunction "-_2") (pintype "passive"))
      (node (ref "C40") (pin "-") (pinfunction "-_-") (pintype "passive"))
      (node (ref "C41") (pin "2") (pinfunction "2_2") (pintype "passive"))
      (node (ref "C42") (pin "-") (pinfunction "-_-") (pintype "passive"))
      (node (ref "C43") (pin "-") (pinfunction "-_-") (pintype "passive"))
      (node (ref "C44") (pin "2") (pinfunction "2_2") (pintype "passive"))
      (node (ref "C7") (pin "2") (pinfunction "-_2") (pintype "passive"))
      (node (ref "C8") (pin "2") (pinfunction "-_2") (pintype "passive"))
      (node (ref "C9") (pin "2") (pinfunction "-_2") (pintype "passive"))
      (node (ref "D10") (pin "C") (pinfunction "C_C") (pintype "passive"))
      (node (ref "D11") (pin "C") (pinfunction "C_C") (pintype "passive"))
      (node (ref "D12") (pin "C") (pinfunction "C_C") (pintype "passive"))
      (node (ref "D15") (pin "C") (pinfunction "C_C") (pintype "passive"))
      (node (ref "D2") (pin "C") (pinfunction "C_C") (pintype "passive"))
      (node (ref "D9") (pin "C") (pinfunction "C_C") (pintype "passive"))
      (node (ref "J14") (pin "4") (pinfunction "GND_4") (pintype "power_in"))
      (node (ref "J3") (pin "7") (pinfunction "7_7") (pintype "passive"))
      (node (ref "J3") (pin "8") (pinfunction "8_8") (pintype "passive"))
      (node (ref "J5") (pin "16") (pinfunction "16_16") (pintype "passive"))
      (node (ref "JP1") (pin "3") (pinfunction "3_3") (pintype "passive"))
      (node (ref "L3") (pin "1") (pinfunction "1_1") (pintype "passive"))
      (node (ref "Q3") (pin "2") (pinfunction "S_2") (pintype "passive"))
      (node (ref "R18") (pin "1") (pinfunction "1_1") (pintype "passive"))
      (node (ref "R20") (pin "1") (pinfunction "1_1") (pintype "passive"))
      (node (ref "R40") (pin "1") (pinfunction "1_1") (pintype "passive"))
      (node (ref "R41") (pin "1") (pinfunction "1_1") (pintype "passive"))
      (node (ref "R54") (pin "1") (pinfunction "1_1") (pintype "passive"))
      (node (ref "R56") (pin "1") (pinfunction "1_1") (pintype "passive"))
      (node (ref "S2") (pin "1") (pinfunction "1_1") (pintype "passive"))
      (node (ref "SJ2") (pin "1") (pinfunction "1_1") (pintype "passive"))
      (node (ref "U1") (pin "5") (pinfunction "GND_5") (pintype "bidirectional"))
      (node (ref "U10") (pin "3") (pinfunction "GND_3") (pintype "bidirectional"))
      (node (ref "U11") (pin "13") (pinfunction "SLOW_13") (pintype "bidirectional"))
      (node (ref "U11") (pin "14") (pinfunction "GND_14") (pintype "bidirectional"))
      (node (ref "U12") (pin "2") (pinfunction "GND_2") (pintype "bidirectional"))
      (node (ref "U12") (pin "5") (pinfunction "WP_5") (pintype "bidirectional"))
      (node (ref "U17") (pin "13") (pinfunction "PGND2_13") (pintype "bidirectional"))
      (node (ref "U17") (pin "4") (pinfunction "PGND1_4") (pintype "bidirectional"))
      (node (ref "U17") (pin "8") (pinfunction "GND_8") (pintype "bidirectional"))
      (node (ref "U17") (pin "EP") (pinfunction "GND_EP") (pintype "bidirectional"))
      (node (ref "U3") (pin "13") (pinfunction "GND_13") (pintype "bidirectional"))
      (node (ref "U3") (pin "5") (pinfunction "GND_5") (pintype "bidirectional"))
      (node (ref "U4") (pin "1") (pinfunction "1~{OE}_1") (pintype "bidirectional"))
      (node (ref "U4") (pin "4") (pinfunction "GND_4") (pintype "bidirectional"))
      (node (ref "U5") (pin "3") (pinfunction "GND_3") (pintype "bidirectional"))
      (node (ref "U6") (pin "16") (pinfunction "AVSS_16") (pintype "bidirectional"))
      (node (ref "U6") (pin "29") (pinfunction "VSS1_29") (pintype "bidirectional"))
      (node (ref "U6") (pin "39") (pinfunction "VSS2_39") (pintype "bidirectional"))
      (node (ref "U6") (pin "6") (pinfunction "VSS_6") (pintype "bidirectional"))
      (node (ref "U7") (pin "5") (pinfunction "S_5") (pintype "passive"))
      (node (ref "U8") (pin "13") (pinfunction "SLOW_13") (pintype "bidirectional"))
      (node (ref "U8") (pin "14") (pinfunction "GND_14") (pintype "bidirectional"))
      (node (ref "U9") (pin "2") (pinfunction "GND_2") (pintype "bidirectional"))
    )
    (net (code "14") (name "HV-SENSE") (class "Default")
      (node (ref "J3") (pin "2") (pinfunction "2_2") (pintype "passive"))
      (node (ref "R21") (pin "2") (pinfunction "2_2") (pintype "passive"))
      (node (ref "U5") (pin "2") (pinfunction "A_2") (pintype "bidirectional"))
      (node (ref "U6") (pin "12") (pinfunction "TMS/PMA10/RA10*_12") (pintype "bidirectional"))
    )
    (net (code "15") (name "IMD") (class "Default")
      (node (ref "J10") (pin "2") (pinfunction "P$2_2") (pintype "bidirectional"))
      (node (ref "J5") (pin "10") (pinfunction "10_10") (pintype "passive"))
      (node (ref "R24") (pin "2") (pinfunction "2_2") (pintype "passive"))
      (node (ref "R34") (pin "2") (pinfunction "2_2") (pintype "passive"))
    )
    (net (code "16") (name "MISO") (class "Default")
      (node (ref "J11") (pin "2") (pinfunction "2_2") (pintype "passive"))
      (node (ref "R29") (pin "1") (pinfunction "1_1") (pintype "passive"))
      (node (ref "U11") (pin "3") (pinfunction "MISO_3") (pintype "bidirectional"))
      (node (ref "U6") (pin "37") (pinfunction "*RP20(1)/CN25/PMA4/RC4_37") (pintype "bidirectional"))
      (node (ref "U8") (pin "3") (pinfunction "MISO_3") (pintype "bidirectional"))
    )
    (net (code "17") (name "MOSI") (class "Default")
      (node (ref "J11") (pin "3") (pinfunction "3_3") (pintype "passive"))
      (node (ref "R30") (pin "1") (pinfunction "1_1") (pintype "passive"))
      (node (ref "U11") (pin "2") (pinfunction "MOSI_2") (pintype "bidirectional"))
      (node (ref "U6") (pin "38") (pinfunction "*RP21(1)/CN26/PMA3/RC5_38") (pintype "bidirectional"))
      (node (ref "U8") (pin "2") (pinfunction "MOSI_2") (pintype "bidirectional"))
    )
    (net (code "18") (name "N$85") (class "Default")
      (node (ref "C14") (pin "A") (pinfunction "+_A") (pintype "passive"))
      (node (ref "C20") (pin "1") (pinfunction "+_1") (pintype "passive"))
      (node (ref "J14") (pin "1") (pinfunction "VBUS_1") (pintype "power_in"))
      (node (ref "U3") (pin "12") (pinfunction "VCC_12") (pintype "bidirectional"))
    )
    (net (code "19") (name "Net-(C2-+)") (class "Default")
      (node (ref "C2") (pin "1") (pinfunction "+_1") (pintype "passive"))
      (node (ref "JP1") (pin "5") (pinfunction "5_5") (pintype "passive"))
      (node (ref "R16") (pin "1") (pinfunction "1_1") (pintype "passive"))
      (node (ref "R3") (pin "1") (pinfunction "1_1") (pintype "passive"))
      (node (ref "S2") (pin "2") (pinfunction "2_2") (pintype "passive"))
      (node (ref "SJ3") (pin "2") (pinfunction "2_2") (pintype "passive"))
    )
    (net (code "20") (name "Net-(C3-+)") (class "Default")
      (node (ref "C3") (pin "1") (pinfunction "+_1") (pintype "passive"))
      (node (ref "U6") (pin "30") (pinfunction "OSC1/CLKI/CN30/RA2_30") (pintype "bidirectional"))
      (node (ref "Y1") (pin "1") (pinfunction "1_1") (pintype "passive"))
    )
    (net (code "21") (name "Net-(C12-+)") (class "Default")
      (node (ref "C12") (pin "A") (pinfunction "+_A") (pintype "passive"))
      (node (ref "U6") (pin "7") (pinfunction "VCAP_7") (pintype "bidirectional"))
    )
    (net (code "22") (name "Net-(C16-+)") (class "Default")
      (node (ref "C16") (pin "1") (pinfunction "+_1") (pintype "passive"))
      (node (ref "R4") (pin "2") (pinfunction "2_2") (pintype "passive"))
      (node (ref "R7") (pin "2") (pinfunction "2_2") (pintype "passive"))
      (node (ref "R8") (pin "2") (pinfunction "2_2") (pintype "passive"))
      (node (ref "U3") (pin "10") (pinfunction "3V3-OUT_10") (pintype "bidirectional"))
      (node (ref "U3") (pin "11") (pinfunction "RESET_11") (pintype "bidirectional"))
      (node (ref "U3") (pin "3") (pinfunction "VCCO_3") (pintype "bidirectional"))
      (node (ref "U4") (pin "8") (pinfunction "VCC_8") (pintype "bidirectional"))
    )
    (net (code "23") (name "Net-(C21-+)") (class "Default")
      (node (ref "C21") (pin "1") (pinfunction "+_1") (pintype "passive"))
      (node (ref "U6") (pin "31") (pinfunction "OSC2/CLKO/CN29/RA3_31") (pintype "bidirectional"))
      (node (ref "Y1") (pin "3") (pinfunction "2_3") (pintype "passive"))
    )
    (net (code "24") (name "Net-(D1-PadA)") (class "Default")
      (node (ref "D1") (pin "A") (pinfunction "A_A") (pintype "passive"))
      (node (ref "R7") (pin "1") (pinfunction "1_1") (pintype "passive"))
    )
    (net (code "25") (name "Net-(D2-PadA)") (class "Default")
      (node (ref "D2") (pin "A") (pinfunction "A_A") (pintype "passive"))
      (node (ref "R13") (pin "1") (pinfunction "1_1") (pintype "passive"))
    )
    (net (code "26") (name "Net-(D3-PadA)") (class "Default")
      (node (ref "D3") (pin "A") (pinfunction "A_A") (pintype "passive"))
      (node (ref "R24") (pin "1") (pinfunction "1_1") (pintype "passive"))
    )
    (net (code "27") (name "Net-(D4-PadA)") (class "Default")
      (node (ref "D4") (pin "A") (pinfunction "A_A") (pintype "bidirectional"))
      (node (ref "J5") (pin "1") (pinfunction "1_1") (pintype "passive"))
    )
    (net (code "28") (name "Net-(D4-PadC)") (class "Default")
      (node (ref "D4") (pin "C") (pinfunction "C_C") (pintype "bidirectional"))
      (node (ref "L2") (pin "2") (pinfunction "2_2") (pintype "passive"))
    )
    (net (code "29") (name "Net-(D7-PadA)") (class "Default")
      (node (ref "D7") (pin "A") (pinfunction "A_A") (pintype "passive"))
      (node (ref "R8") (pin "1") (pinfunction "1_1") (pintype "passive"))
    )
    (net (code "30") (name "Net-(D9-PadA)") (class "Default")
      (node (ref "D9") (pin "A") (pinfunction "A_A") (pintype "passive"))
      (node (ref "R12") (pin "1") (pinfunction "1_1") (pintype "passive"))
    )
    (net (code "31") (name "Net-(D10-PadA)") (class "Default")
      (node (ref "D10") (pin "A") (pinfunction "A_A") (pintype "passive"))
      (node (ref "R23") (pin "1") (pinfunction "1_1") (pintype "passive"))
    )
    (net (code "32") (name "Net-(D11-PadA)") (class "Default")
      (node (ref "D11") (pin "A") (pinfunction "A_A") (pintype "passive"))
      (node (ref "R26") (pin "1") (pinfunction "1_1") (pintype "passive"))
    )
    (net (code "33") (name "Net-(D12-PadA)") (class "Default")
      (node (ref "D12") (pin "A") (pinfunction "A_A") (pintype "passive"))
      (node (ref "R25") (pin "2") (pinfunction "2_2") (pintype "passive"))
    )
    (net (code "34") (name "Net-(D13-PadA)") (class "Default")
      (node (ref "D13") (pin "A") (pinfunction "A_A") (pintype "passive"))
      (node (ref "R6") (pin "1") (pinfunction "1_1") (pintype "passive"))
    )
    (net (code "35") (name "Net-(D14-PadA)") (class "Default")
      (node (ref "D14") (pin "A") (pinfunction "A_A") (pintype "passive"))
      (node (ref "R9") (pin "1") (pinfunction "1_1") (pintype "passive"))
    )
    (net (code "36") (name "Net-(D15-PadA)") (class "Default")
      (node (ref "D15") (pin "A") (pinfunction "A_A") (pintype "passive"))
      (node (ref "R27") (pin "1") (pinfunction "1_1") (pintype "passive"))
    )
    (net (code "37") (name "Net-(F1-P$2)") (class "Default")
      (node (ref "F1") (pin "2") (pinfunction "P$2_2") (pintype "bidirectional"))
      (node (ref "Q1") (pin "2") (pinfunction "D_2") (pintype "passive"))
      (node (ref "R27") (pin "2") (pinfunction "2_2") (pintype "passive"))
    )
    (net (code "38") (name "Net-(J1-Pad1)") (class "Default")
      (node (ref "J1") (pin "1") (pinfunction "1_1") (pintype "passive"))
      (node (ref "TX3") (pin "4") (pinfunction "4_4") (pintype "bidirectional"))
    )
    (net (code "39") (name "Net-(J1-Pad2)") (class "Default")
      (node (ref "J1") (pin "2") (pinfunction "2_2") (pintype "passive"))
      (node (ref "TX3") (pin "6") (pinfunction "6_6") (pintype "bidirectional"))
    )
    (net (code "40") (name "Net-(J2-Pad1)") (class "Default")
      (node (ref "J2") (pin "1") (pinfunction "1_1") (pintype "passive"))
      (node (ref "TX4") (pin "4") (pinfunction "4_4") (pintype "bidirectional"))
    )
    (net (code "41") (name "Net-(J2-Pad2)") (class "Default")
      (node (ref "J2") (pin "2") (pinfunction "2_2") (pintype "passive"))
      (node (ref "TX4") (pin "6") (pinfunction "6_6") (pintype "bidirectional"))
    )
    (net (code "42") (name "Net-(J5-Pad4)") (class "Default")
      (node (ref "J5") (pin "4") (pinfunction "4_4") (pintype "passive"))
      (node (ref "L3") (pin "2") (pinfunction "2_2") (pintype "passive"))
    )
    (net (code "43") (name "Net-(J5-Pad11)") (class "Default")
      (node (ref "J5") (pin "11") (pinfunction "11_11") (pintype "passive"))
      (node (ref "J8") (pin "2") (pinfunction "2_2") (pintype "passive"))
    )
    (net (code "44") (name "Net-(J5-Pad12)") (class "Default")
      (node (ref "J5") (pin "12") (pinfunction "12_12") (pintype "passive"))
      (node (ref "J8") (pin "1") (pinfunction "1_1") (pintype "passive"))
    )
    (net (code "45") (name "Net-(J14-D+)") (class "Default")
      (node (ref "J14") (pin "3") (pinfunction "D+_3") (pintype "bidirectional"))
      (node (ref "U3") (pin "8") (pinfunction "DP_8") (pintype "bidirectional"))
    )
    (net (code "46") (name "Net-(J14-D-)") (class "Default")
      (node (ref "J14") (pin "2") (pinfunction "D-_2") (pintype "bidirectional"))
      (node (ref "U3") (pin "9") (pinfunction "DM_9") (pintype "bidirectional"))
    )
    (net (code "47") (name "Net-(K1A-+1)") (class "Default")
      (node (ref "K1") (pin "-8-S") (pinfunction "+1_-8-S") (pintype "passive"))
      (node (ref "U23") (pin "6") (pinfunction "D_6") (pintype "passive"))
    )
    (net (code "48") (name "Net-(K1A-+2)") (class "Default")
      (node (ref "K1") (pin "-9-R") (pinfunction "+2_-9-R") (pintype "passive"))
      (node (ref "U23") (pin "3") (pinfunction "D_3") (pintype "passive"))
    )
    (net (code "49") (name "Net-(Q1-G)") (class "Default")
      (node (ref "Q1") (pin "1") (pinfunction "G_1") (pintype "passive"))
      (node (ref "R10") (pin "1") (pinfunction "1_1") (pintype "passive"))
      (node (ref "R28") (pin "2") (pinfunction "2_2") (pintype "passive"))
    )
    (net (code "50") (name "Net-(Q3-D)") (class "Default")
      (node (ref "Q3") (pin "3") (pinfunction "D_3") (pintype "passive"))
      (node (ref "R28") (pin "1") (pinfunction "1_1") (pintype "passive"))
    )
    (net (code "51") (name "Net-(Q3-G)") (class "Default")
      (node (ref "Q3") (pin "1") (pinfunction "G_1") (pintype "passive"))
      (node (ref "R11") (pin "2") (pinfunction "2_2") (pintype "passive"))
      (node (ref "R20") (pin "2") (pinfunction "2_2") (pintype "passive"))
    )
    (net (code "52") (name "Net-(U1-A)") (class "Default")
      (node (ref "J5") (pin "3") (pinfunction "3_3") (pintype "passive"))
      (node (ref "R2") (pin "2") (pinfunction "2_2") (pintype "passive"))
      (node (ref "U1") (pin "6") (pinfunction "A_6") (pintype "bidirectional"))
    )
    (net (code "53") (name "Net-(U1-B)") (class "Default")
      (node (ref "J5") (pin "2") (pinfunction "2_2") (pintype "passive"))
      (node (ref "R2") (pin "1") (pinfunction "1_1") (pintype "passive"))
      (node (ref "U1") (pin "7") (pinfunction "B_7") (pintype "bidirectional"))
    )
    (net (code "54") (name "Net-(U3-CBUS1)") (class "Default")
      (node (ref "D1") (pin "C") (pinfunction "C_C") (pintype "passive"))
      (node (ref "U3") (pin "14") (pinfunction "CBUS1_14") (pintype "bidirectional"))
    )
    (net (code "55") (name "Net-(U3-CBUS2)") (class "Default")
      (node (ref "D7") (pin "C") (pinfunction "C_C") (pintype "passive"))
      (node (ref "U3") (pin "7") (pinfunction "CBUS2_7") (pintype "bidirectional"))
    )
    (net (code "56") (name "Net-(U3-CBUS3)") (class "Default")
      (node (ref "SJ2") (pin "2") (pinfunction "2_2") (pintype "passive"))
      (node (ref "U3") (pin "16") (pinfunction "CBUS3_16") (pintype "bidirectional"))
    )
    (net (code "57") (name "Net-(U3-RXD)") (class "Default")
      (node (ref "U3") (pin "4") (pinfunction "RXD_4") (pintype "bidirectional"))
      (node (ref "U4") (pin "3") (pinfunction "2Y_3") (pintype "bidirectional"))
    )
    (net (code "58") (name "Net-(U3-TXD)") (class "Default")
      (node (ref "U3") (pin "1") (pinfunction "TXD_1") (pintype "bidirectional"))
      (node (ref "U4") (pin "2") (pinfunction "1A_2") (pintype "bidirectional"))
    )
    (net (code "59") (name "Net-(U4-2OE)") (class "Default")
      (node (ref "R4") (pin "1") (pinfunction "1_1") (pintype "passive"))
      (node (ref "U4") (pin "7") (pinfunction "2OE_7") (pintype "bidirectional"))
    )
    (net (code "60") (name "Net-(U5-Y)") (class "Default")
      (node (ref "R11") (pin "1") (pinfunction "1_1") (pintype "passive"))
      (node (ref "U5") (pin "4") (pinfunction "Y_4") (pintype "bidirectional"))
    )
    (net (code "61") (name "Net-(U6-PGEC1{slash}AN3{slash}C2IN+{slash}RP1(1){slash}CN5{slash}RB1)") (class "Default")
      (node (ref "R25") (pin "1") (pinfunction "1_1") (pintype "passive"))
      (node (ref "U6") (pin "22") (pinfunction "PGEC1/AN3/C2IN+/RP1(1)/CN5/RB1_22") (pintype "bidirectional"))
    )
    (net (code "62") (name "Net-(U6-PGEC2{slash}RP11(1){slash}CN15{slash}PMD1{slash}RB11*)") (class "Default")
      (node (ref "JP1") (pin "1") (pinfunction "1_1") (pintype "passive"))
      (node (ref "U6") (pin "9") (pinfunction "PGEC2/RP11(1)/CN15/PMD1/RB11*_9") (pintype "bidirectional"))
    )
    (net (code "63") (name "Net-(U6-PGED2{slash}EMCD2{slash}RP10(1){slash}CN16{slash}PMD2{slash}RB10*)") (class "Default")
      (node (ref "JP1") (pin "2") (pinfunction "2_2") (pintype "passive"))
      (node (ref "U6") (pin "8") (pinfunction "PGED2/EMCD2/RP10(1)/CN16/PMD2/RB10*_8") (pintype "bidirectional"))
    )
    (net (code "64") (name "Net-(U6-~{MCLR}*)") (class "Default")
      (node (ref "R16") (pin "2") (pinfunction "2_2") (pintype "passive"))
      (node (ref "U6") (pin "18") (pinfunction "~{MCLR}*_18") (pintype "bidirectional"))
    )
    (net (code "65") (name "Net-(U7A-D)") (class "Default")
      (node (ref "R5") (pin "1") (pinfunction "1_1") (pintype "passive"))
      (node (ref "U7") (pin "6") (pinfunction "D_6") (pintype "passive"))
    )
    (net (code "66") (name "Net-(U7A-G)") (class "Default")
      (node (ref "R18") (pin "2") (pinfunction "2_2") (pintype "passive"))
      (node (ref "R22") (pin "2") (pinfunction "2_2") (pintype "passive"))
      (node (ref "U7") (pin "1") (pinfunction "G_1") (pintype "passive"))
    )
    (net (code "67") (name "Net-(U7B-D)") (class "Default")
      (node (ref "R15") (pin "2") (pinfunction "2_2") (pintype "passive"))
      (node (ref "U7") (pin "4") (pinfunction "D_4") (pintype "passive"))
    )
    (net (code "68") (name "Net-(U7B-G)") (class "Default")
      (node (ref "R14") (pin "1") (pinfunction "1_1") (pintype "passive"))
      (node (ref "R5") (pin "2") (pinfunction "2_2") (pintype "passive"))
      (node (ref "U7") (pin "3") (pinfunction "G_3") (pintype "passive"))
    )
    (net (code "69") (name "Net-(U8-IBIAS)") (class "Default")
      (node (ref "R53") (pin "1") (pinfunction "1_1") (pintype "passive"))
      (node (ref "U8") (pin "16") (pinfunction "IBIAS_16") (pintype "bidirectional"))
    )
    (net (code "70") (name "Net-(U8-ICMP)") (class "Default")
      (node (ref "R53") (pin "2") (pinfunction "2_2") (pintype "passive"))
      (node (ref "R54") (pin "2") (pinfunction "2_2") (pintype "passive"))
      (node (ref "U8") (pin "15") (pinfunction "ICMP_15") (pintype "bidirectional"))
    )
    (net (code "71") (name "Net-(U8-IM)") (class "Default")
      (node (ref "R17") (pin "2") (pinfunction "2_2") (pintype "passive"))
      (node (ref "TX3") (pin "3") (pinfunction "3_3") (pintype "bidirectional"))
      (node (ref "U8") (pin "10") (pinfunction "IM_10") (pintype "bidirectional"))
    )
    (net (code "72") (name "Net-(U8-IP)") (class "Default")
      (node (ref "R17") (pin "1") (pinfunction "1_1") (pintype "passive"))
      (node (ref "TX3") (pin "1") (pinfunction "1_1") (pintype "bidirectional"))
      (node (ref "U8") (pin "11") (pinfunction "IP_11") (pintype "bidirectional"))
    )
    (net (code "73") (name "Net-(U9-~{RST})") (class "Default")
      (node (ref "SJ3") (pin "1") (pinfunction "1_1") (pintype "passive"))
      (node (ref "U9") (pin "1") (pinfunction "~{RST}_1") (pintype "bidirectional"))
    )
    (net (code "74") (name "Net-(U10-Y)") (class "Default")
      (node (ref "R22") (pin "1") (pinfunction "1_1") (pintype "passive"))
      (node (ref "U10") (pin "4") (pinfunction "Y_4") (pintype "bidirectional"))
    )
    (net (code "75") (name "Net-(U11-IBIAS)") (class "Default")
      (node (ref "R55") (pin "1") (pinfunction "1_1") (pintype "passive"))
      (node (ref "U11") (pin "16") (pinfunction "IBIAS_16") (pintype "bidirectional"))
    )
    (net (code "76") (name "Net-(U11-ICMP)") (class "Default")
      (node (ref "R55") (pin "2") (pinfunction "2_2") (pintype "passive"))
      (node (ref "R56") (pin "2") (pinfunction "2_2") (pintype "passive"))
      (node (ref "U11") (pin "15") (pinfunction "ICMP_15") (pintype "bidirectional"))
    )
    (net (code "77") (name "Net-(U11-IM)") (class "Default")
      (node (ref "R1") (pin "2") (pinfunction "2_2") (pintype "passive"))
      (node (ref "TX4") (pin "3") (pinfunction "3_3") (pintype "bidirectional"))
      (node (ref "U11") (pin "10") (pinfunction "IM_10") (pintype "bidirectional"))
    )
    (net (code "78") (name "Net-(U11-IP)") (class "Default")
      (node (ref "R1") (pin "1") (pinfunction "1_1") (pintype "passive"))
      (node (ref "TX4") (pin "1") (pinfunction "1_1") (pintype "bidirectional"))
      (node (ref "U11") (pin "11") (pinfunction "IP_11") (pintype "bidirectional"))
    )
    (net (code "79") (name "Net-(U17-SS1)") (class "Default")
      (node (ref "C41") (pin "1") (pinfunction "1_1") (pintype "passive"))
      (node (ref "U17") (pin "6") (pinfunction "SS1_6") (pintype "bidirectional"))
    )
    (net (code "80") (name "Net-(U17-SS2)") (class "Default")
      (node (ref "C44") (pin "1") (pinfunction "1_1") (pintype "passive"))
      (node (ref "U17") (pin "11") (pinfunction "SS2_11") (pintype "bidirectional"))
    )
    (net (code "81") (name "Net-(U17-SW1)") (class "Default")
      (node (ref "C36") (pin "2") (pinfunction "2_2") (pintype "passive"))
      (node (ref "L5") (pin "2") (pinfunction "2_2") (pintype "passive"))
      (node (ref "U17") (pin "3") (pinfunction "SW1_3") (pintype "bidirectional"))
    )
    (net (code "82") (name "Net-(U17-SW2)") (class "Default")
      (node (ref "C37") (pin "2") (pinfunction "2_2") (pintype "passive"))
      (node (ref "L6") (pin "1") (pinfunction "1_1") (pintype "passive"))
      (node (ref "U17") (pin "14") (pinfunction "SW2_14") (pintype "bidirectional"))
    )
    (net (code "83") (name "Net-(U17-VBST1)") (class "Default")
      (node (ref "C36") (pin "1") (pinfunction "1_1") (pintype "passive"))
      (node (ref "U17") (pin "2") (pinfunction "VBST1_2") (pintype "bidirectional"))
    )
    (net (code "84") (name "Net-(U17-VBST2)") (class "Default")
      (node (ref "C37") (pin "1") (pinfunction "1_1") (pintype "passive"))
      (node (ref "U17") (pin "15") (pinfunction "VBST2_15") (pintype "bidirectional"))
    )
    (net (code "85") (name "Net-(U17-VFB1)") (class "Default")
      (node (ref "R39") (pin "1") (pinfunction "1_1") (pintype "passive"))
      (node (ref "R40") (pin "2") (pinfunction "2_2") (pintype "passive"))
      (node (ref "U17") (pin "7") (pinfunction "VFB1_7") (pintype "bidirectional"))
    )
    (net (code "86") (name "Net-(U17-VFB2)") (class "Default")
      (node (ref "R41") (pin "2") (pinfunction "2_2") (pintype "passive"))
      (node (ref "R42") (pin "1") (pinfunction "1_1") (pintype "passive"))
      (node (ref "U17") (pin "10") (pinfunction "VFB2_10") (pintype "bidirectional"))
    )
    (net (code "87") (name "Net-(U17-VREG5)") (class "Default")
      (node (ref "C38") (pin "1") (pinfunction "1_1") (pintype "passive"))
      (node (ref "U17") (pin "9") (pinfunction "VREG5_9") (pintype "bidirectional"))
    )
    (net (code "88") (name "PRE_CRG-B_AIR") (class "Default")
      (node (ref "J5") (pin "15") (pinfunction "15_15") (pintype "passive"))
      (node (ref "J7") (pin "1") (pinfunction "1_1") (pintype "passive"))
      (node (ref "J9") (pin "1") (pinfunction "1_1") (pintype "passive"))
    )
    (net (code "89") (name "RE") (class "Default")
      (node (ref "RE") (pin "1") (pinfunction "P$1_1") (pintype "bidirectional"))
      (node (ref "RE") (pin "2") (pinfunction "P$1_2") (pintype "bidirectional"))
      (node (ref "U1") (pin "2") (pinfunction "~{RE}_2") (pintype "bidirectional"))
      (node (ref "U1") (pin "3") (pinfunction "DE_3") (pintype "bidirectional"))
      (node (ref "U6") (pin "43") (pinfunction "*INT0/RP7(1)/CN23/PMD5/RB7_43") (pintype "bidirectional"))
    )
    (net (code "90") (name "RX2") (class "Default")
      (node (ref "D14") (pin "C") (pinfunction "C_C") (pintype "passive"))
      (node (ref "RX") (pin "1") (pinfunction "P$1_1") (pintype "bidirectional"))
      (node (ref "RX") (pin "2") (pinfunction "P$1_2") (pintype "bidirectional"))
      (node (ref "U1") (pin "1") (pinfunction "R_1") (pintype "bidirectional"))
      (node (ref "U6") (pin "5") (pinfunction "RP25(1)/CN19/PMA6/RC9*_5") (pintype "bidirectional"))
    )
    (net (code "91") (name "SCK") (class "Default")
      (node (ref "J11") (pin "1") (pinfunction "1_1") (pintype "passive"))
      (node (ref "R31") (pin "1") (pinfunction "1_1") (pintype "passive"))
      (node (ref "U11") (pin "4") (pinfunction "SCK_4") (pintype "bidirectional"))
      (node (ref "U6") (pin "36") (pinfunction "*RP19(1)/CN28/PMBE/RC3_36") (pintype "bidirectional"))
      (node (ref "U8") (pin "4") (pinfunction "SCK_4") (pintype "bidirectional"))
    )
    (net (code "92") (name "SCL") (class "Default")
      (node (ref "J3") (pin "5") (pinfunction "5_5") (pintype "passive"))
      (node (ref "R32") (pin "2") (pinfunction "2_2") (pintype "passive"))
      (node (ref "U12") (pin "1") (pinfunction "SCL_1") (pintype "bidirectional"))
      (node (ref "U6") (pin "44") (pinfunction "*SCL1/RP8(1)/CN22/PMD4/RB8_44") (pintype "bidirectional"))
    )
    (net (code "93") (name "SDA") (class "Default")
      (node (ref "J3") (pin "4") (pinfunction "4_4") (pintype "passive"))
      (node (ref "R33") (pin "2") (pinfunction "2_2") (pintype "passive"))
      (node (ref "U12") (pin "3") (pinfunction "SDA_3") (pintype "bidirectional"))
      (node (ref "U6") (pin "1") (pinfunction "SDA1/RP9/CN21/PMD3/RB9*_1") (pintype "bidirectional"))
    )
    (net (code "94") (name "TOP_AIR") (class "Default")
      (node (ref "J5") (pin "14") (pinfunction "14_14") (pintype "passive"))
      (node (ref "J6") (pin "1") (pinfunction "1_1") (pintype "passive"))
    )
    (net (code "95") (name "TSAL") (class "Default")
      (node (ref "F1") (pin "1") (pinfunction "P$1_1") (pintype "bidirectional"))
      (node (ref "J5") (pin "8") (pinfunction "8_8") (pintype "passive"))
    )
    (net (code "96") (name "TX2") (class "Default")
      (node (ref "D13") (pin "C") (pinfunction "C_C") (pintype "passive"))
      (node (ref "TX") (pin "1") (pinfunction "P$1_1") (pintype "bidirectional"))
      (node (ref "TX") (pin "2") (pinfunction "P$1_2") (pintype "bidirectional"))
      (node (ref "U1") (pin "4") (pinfunction "D_4") (pintype "bidirectional"))
      (node (ref "U6") (pin "4") (pinfunction "RP24(1)/CN20/PMA5/RC8*_4") (pintype "bidirectional"))
    )
    (net (code "97") (name "USB_RX") (class "Default")
      (node (ref "U4") (pin "5") (pinfunction "2A_5") (pintype "bidirectional"))
      (node (ref "U6") (pin "2") (pinfunction "RP22(1)/CN18/PMA1/RC6*_2") (pintype "bidirectional"))
    )
    (net (code "98") (name "USB_TX") (class "Default")
      (node (ref "U4") (pin "6") (pinfunction "1Y_6") (pintype "bidirectional"))
      (node (ref "U6") (pin "3") (pinfunction "RP23(1)/CN17/PMA0/RC7*_3") (pintype "bidirectional"))
    )
    (net (code "99") (name "VSS") (class "Default")
      (node (ref "D3") (pin "C") (pinfunction "C_C") (pintype "passive"))
      (node (ref "J10") (pin "3") (pinfunction "P$3_3") (pintype "bidirectional"))
      (node (ref "J5") (pin "13") (pinfunction "13_13") (pintype "passive"))
      (node (ref "J6") (pin "2") (pinfunction "2_2") (pintype "passive"))
      (node (ref "J7") (pin "2") (pinfunction "2_2") (pintype "passive"))
      (node (ref "J9") (pin "2") (pinfunction "2_2") (pintype "passive"))
      (node (ref "R34") (pin "1") (pinfunction "1_1") (pintype "passive"))
      (node (ref "R35") (pin "1") (pinfunction "1_1") (pintype "passive"))
      (node (ref "R36") (pin "1") (pinfunction "1_1") (pintype "passive"))
      (node (ref "U23") (pin "1") (pinfunction "S_1") (pintype "passive"))
      (node (ref "U23") (pin "4") (pinfunction "S_4") (pintype "passive"))
    )
    (net (code "100") (name "WDI") (class "Default")
      (node (ref "U6") (pin "10") (pinfunction "AN12/DAC1RP/RP12(1)/CN14/PMD0/RB12_10") (pintype "bidirectional"))
      (node (ref "U9") (pin "4") (pinfunction "WDI_4") (pintype "bidirectional"))
    )
    (net (code "101") (name "unconnected-(J5-Pad6)") (class "Default")
      (node (ref "J5") (pin "6") (pinfunction "6_6") (pintype "passive"))
    )
    (net (code "102") (name "unconnected-(J5-Pad7)") (class "Default")
      (node (ref "J5") (pin "7") (pinfunction "7_7") (pintype "passive"))
    )
    (net (code "103") (name "unconnected-(J14-ID-PadS1)") (class "Default")
      (node (ref "J14") (pin "S1") (pinfunction "ID_S1") (pintype "bidirectional"))
    )
    (net (code "104") (name "unconnected-(U3-CBUS0-Pad15)") (class "Default")
      (node (ref "U3") (pin "15") (pinfunction "CBUS0_15") (pintype "bidirectional"))
    )
    (net (code "105") (name "unconnected-(U6-*PGEC3{slash}ASCL1{slash}RP6(1){slash}CN24{slash}PMD6{slash}RB6-Pad42)") (class "Default")
      (node (ref "U6") (pin "42") (pinfunction "*PGEC3/ASCL1/RP6(1)/CN24/PMD6/RB6_42") (pintype "bidirectional"))
    )
    (net (code "106") (name "unconnected-(U6-*PGED3{slash}ASDA1{slash}RP5(1){slash}CN27{slash}PMD7{slash}RB5-Pad41)") (class "Default")
      (node (ref "U6") (pin "41") (pinfunction "*PGED3/ASDA1/RP5(1)/CN27/PMD7/RB5_41") (pintype "bidirectional"))
    )
    (net (code "107") (name "unconnected-(U6-AN0{slash}VREF+{slash}CN2{slash}RA0-Pad19)") (class "Default")
      (node (ref "U6") (pin "19") (pinfunction "AN0/VREF+/CN2/RA0_19") (pintype "bidirectional"))
    )
    (net (code "108") (name "unconnected-(U6-AN1{slash}VREF-{slash}CN3{slash}RA1-Pad20)") (class "Default")
      (node (ref "U6") (pin "20") (pinfunction "AN1/VREF-/CN3/RA1_20") (pintype "bidirectional"))
    )
    (net (code "109") (name "unconnected-(U6-AN6{slash}DAC1RM{slash}RP16(1){slash}CN8{slash}RC0-Pad25)") (class "Default")
      (node (ref "U6") (pin "25") (pinfunction "AN6/DAC1RM/RP16(1)/CN8/RC0_25") (pintype "bidirectional"))
    )
    (net (code "110") (name "unconnected-(U6-AN7{slash}DAC1LM{slash}RP17{slash}(1){slash}CN9{slash}RC1-Pad26)") (class "Default")
      (node (ref "U6") (pin "26") (pinfunction "AN7/DAC1LM/RP17/(1)/CN9/RC1_26") (pintype "bidirectional"))
    )
    (net (code "111") (name "unconnected-(U6-AN8{slash}CVREF{slash}RP18(1){slash}PMA2{slash}CN10{slash}RC2-Pad27)") (class "Default")
      (node (ref "U6") (pin "27") (pinfunction "AN8/CVREF/RP18(1)/PMA2/CN10/RC2_27") (pintype "bidirectional"))
    )
    (net (code "112") (name "unconnected-(U6-AN9{slash}DAC1LN{slash}RP15(1){slash}CN11{slash}PMCS1{slash}RB15*-Pad15)") (class "Default")
      (node (ref "U6") (pin "15") (pinfunction "AN9/DAC1LN/RP15(1)/CN11/PMCS1/RB15*_15") (pintype "bidirectional"))
    )
    (net (code "113") (name "unconnected-(U6-AN10{slash}DAC1LP{slash}RTCC{slash}RP14*-Pad14)") (class "Default")
      (node (ref "U6") (pin "14") (pinfunction "AN10/DAC1LP/RTCC/RP14*_14") (pintype "bidirectional"))
    )
    (net (code "114") (name "unconnected-(U6-AN11{slash}DAC1RN{slash}RP13(1){slash}CN13{slash}PMRD{slash}RB13-Pad11)") (class "Default")
      (node (ref "U6") (pin "11") (pinfunction "AN11/DAC1RN/RP13(1)/CN13/PMRD/RB13_11") (pintype "bidirectional"))
    )
    (net (code "115") (name "unconnected-(U6-PGED1{slash}AN2{slash}C2IN-{slash}RP0(1){slash}CN4{slash}RB0-Pad21)") (class "Default")
      (node (ref "U6") (pin "21") (pinfunction "PGED1/AN2/C2IN-/RP0(1)/CN4/RB0_21") (pintype "bidirectional"))
    )
    (net (code "116") (name "unconnected-(U6-TCK{slash}PMA7{slash}RA7*-Pad13)") (class "Default")
      (node (ref "U6") (pin "13") (pinfunction "TCK/PMA7/RA7*_13") (pintype "bidirectional"))
    )
    (net (code "117") (name "unconnected-(U9-~{MR}-Pad3)") (class "Default")
      (node (ref "U9") (pin "3") (pinfunction "~{MR}_3") (pintype "bidirectional"))
    )
  )
)
